# SAMC21N_Xplained_Pro_Level_Converters.net
KiCad netlist of a schematic drawn in Altium Designer
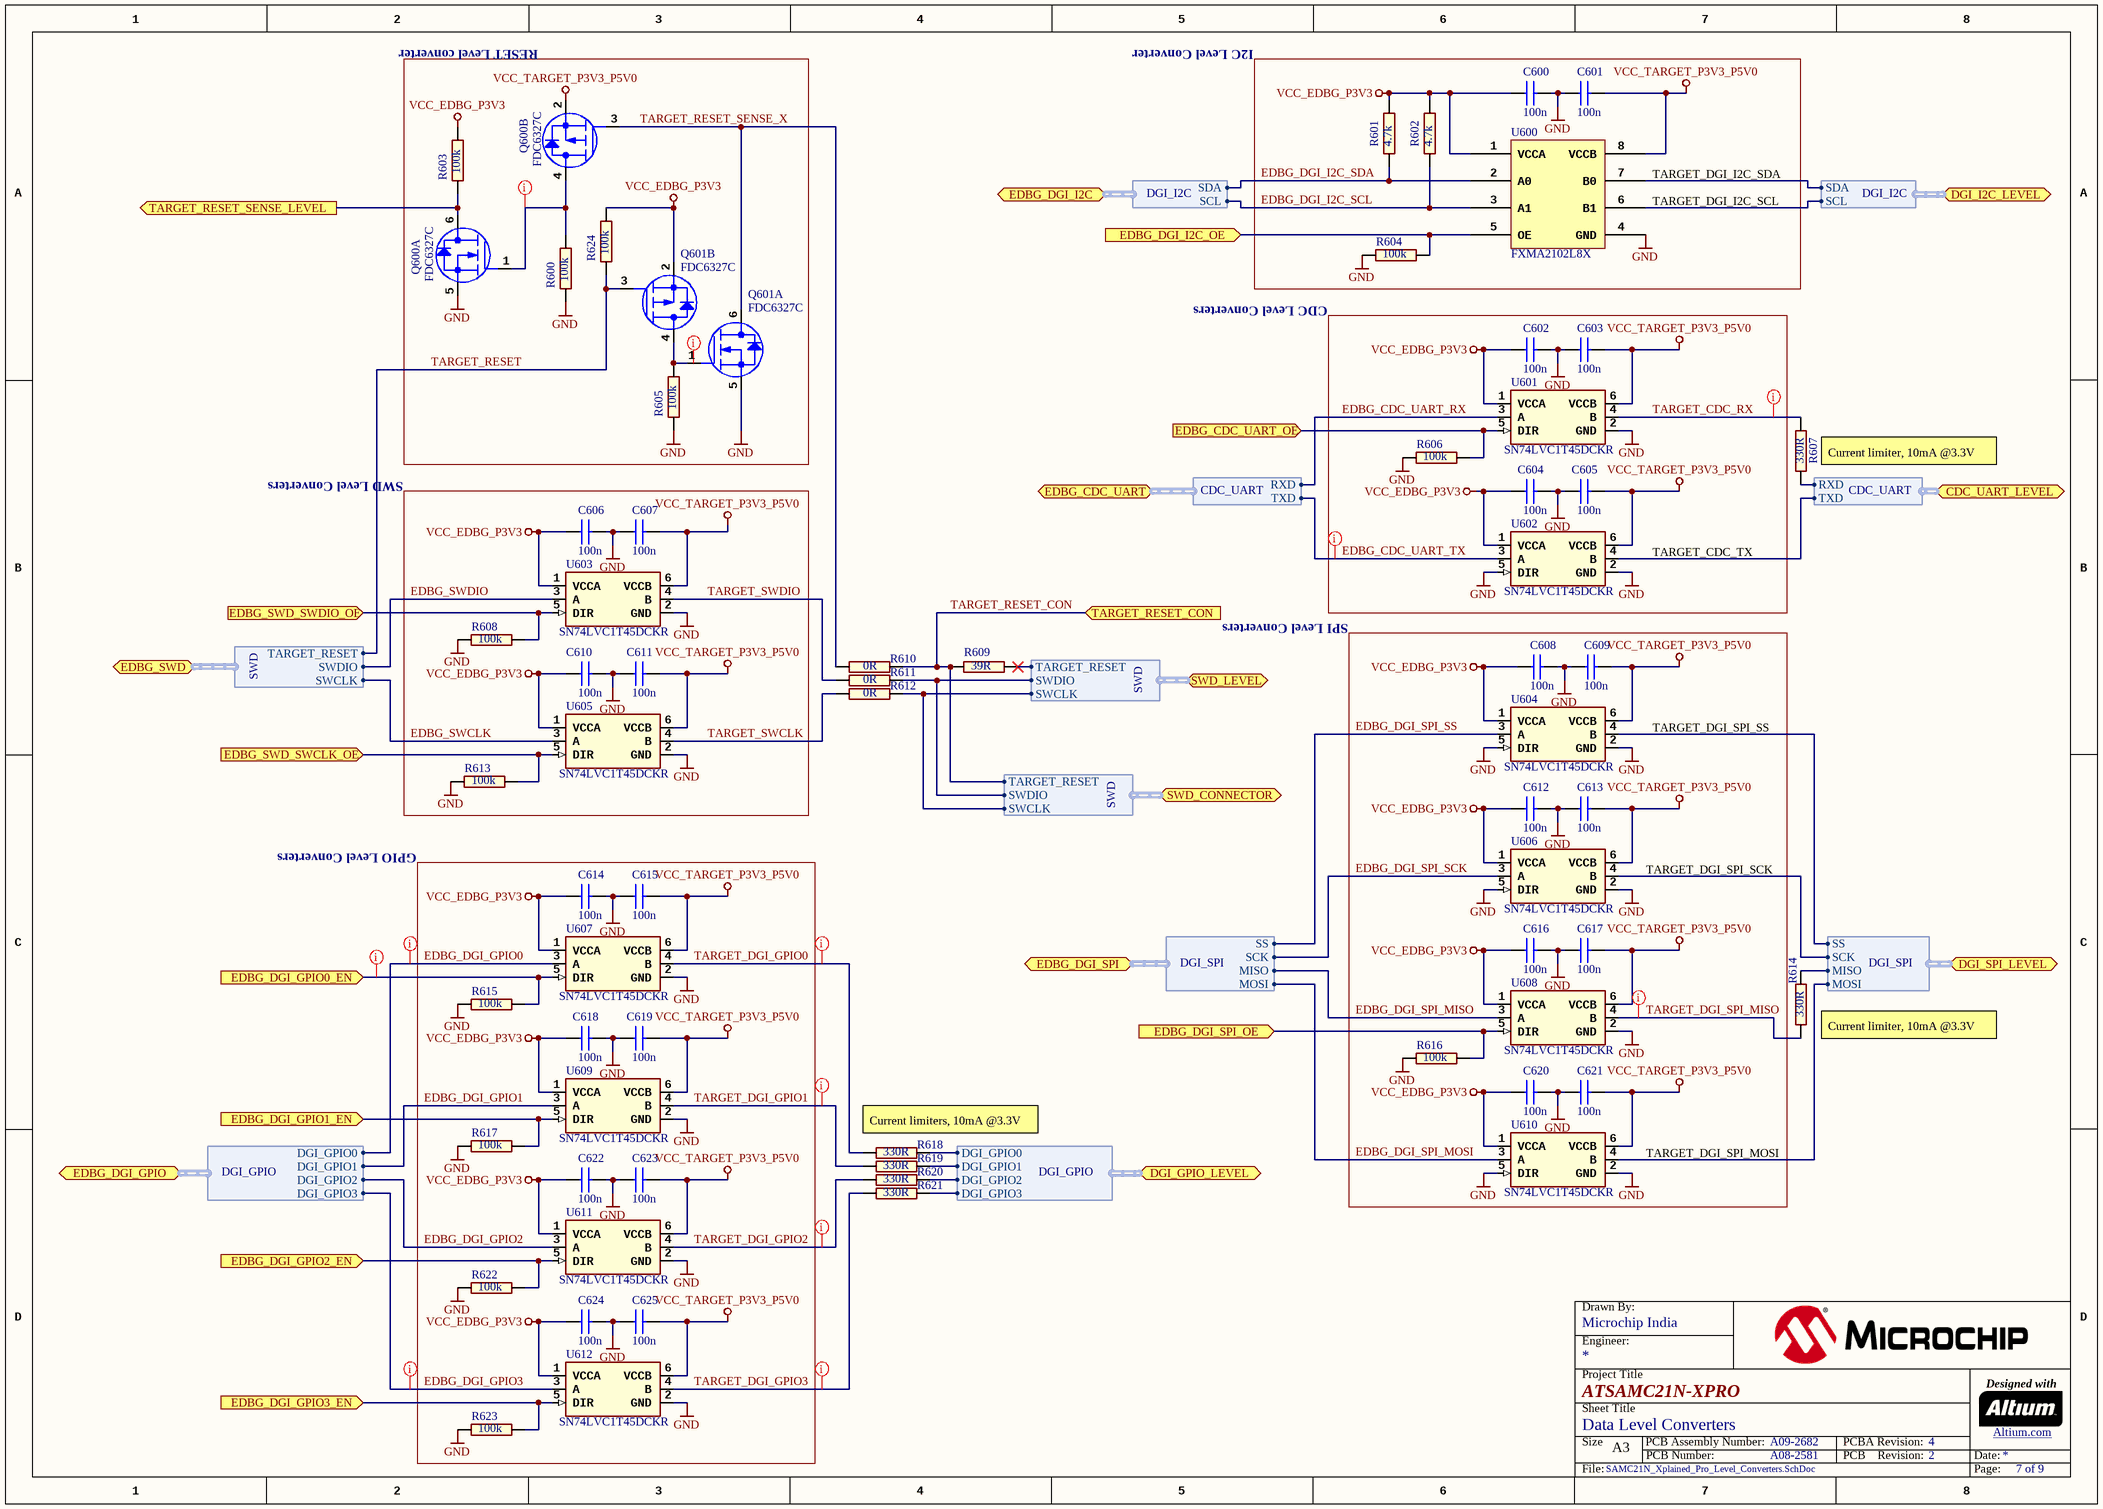
[diagram p0: SAMC21N_Xplained_Pro_Level_Converters.SchDoc]

(export (version "E")
  (design (tool "Eeschema 10.0.6"))
  (components
    (comp (ref "C600")
      (value "100n")
      (footprint "AP1-00053")
      (description "Ceramic capacitor, SMD 0402, X7R, 16V, +/-10%")
      (fields
        (field (name "TOLERANCE") "16V, +/-10%")
        (field (name "MANUFACTURER") "Kemet")
        (field (name "VERIFIED BY") "Lars Helge Mo")
      )
      (libsource (lib "AltiumDbLib") (part "CAP-NONPOL"))
    )
    (comp (ref "C601")
      (value "100n")
      (footprint "AP1-00053")
      (description "Ceramic capacitor, SMD 0402, X7R, 16V, +/-10%")
      (fields
        (field (name "TOLERANCE") "16V, +/-10%")
        (field (name "MANUFACTURER") "Kemet")
        (field (name "VERIFIED BY") "Lars Helge Mo")
      )
      (libsource (lib "AltiumDbLib") (part "CAP-NONPOL"))
    )
    (comp (ref "C602")
      (value "100n")
      (footprint "AP1-00053")
      (description "Ceramic capacitor, SMD 0402, X7R, 16V, +/-10%")
      (fields
        (field (name "TOLERANCE") "16V, +/-10%")
        (field (name "MANUFACTURER") "Kemet")
        (field (name "VERIFIED BY") "Lars Helge Mo")
      )
      (libsource (lib "AltiumDbLib") (part "CAP-NONPOL"))
    )
    (comp (ref "C603")
      (value "100n")
      (footprint "AP1-00053")
      (description "Ceramic capacitor, SMD 0402, X7R, 16V, +/-10%")
      (fields
        (field (name "TOLERANCE") "16V, +/-10%")
        (field (name "MANUFACTURER") "Kemet")
        (field (name "VERIFIED BY") "Lars Helge Mo")
      )
      (libsource (lib "AltiumDbLib") (part "CAP-NONPOL"))
    )
    (comp (ref "C604")
      (value "100n")
      (footprint "AP1-00053")
      (description "Ceramic capacitor, SMD 0402, X7R, 16V, +/-10%")
      (fields
        (field (name "TOLERANCE") "16V, +/-10%")
        (field (name "MANUFACTURER") "Kemet")
        (field (name "VERIFIED BY") "Lars Helge Mo")
      )
      (libsource (lib "AltiumDbLib") (part "CAP-NONPOL"))
    )
    (comp (ref "C605")
      (value "100n")
      (footprint "AP1-00053")
      (description "Ceramic capacitor, SMD 0402, X7R, 16V, +/-10%")
      (fields
        (field (name "TOLERANCE") "16V, +/-10%")
        (field (name "MANUFACTURER") "Kemet")
        (field (name "VERIFIED BY") "Lars Helge Mo")
      )
      (libsource (lib "AltiumDbLib") (part "CAP-NONPOL"))
    )
    (comp (ref "C606")
      (value "100n")
      (footprint "AP1-00053")
      (description "Ceramic capacitor, SMD 0402, X7R, 16V, +/-10%")
      (fields
        (field (name "TOLERANCE") "16V, +/-10%")
        (field (name "MANUFACTURER") "Kemet")
        (field (name "VERIFIED BY") "Lars Helge Mo")
      )
      (libsource (lib "AltiumDbLib") (part "CAP-NONPOL"))
    )
    (comp (ref "C607")
      (value "100n")
      (footprint "AP1-00053")
      (description "Ceramic capacitor, SMD 0402, X7R, 16V, +/-10%")
      (fields
        (field (name "TOLERANCE") "16V, +/-10%")
        (field (name "MANUFACTURER") "Kemet")
        (field (name "VERIFIED BY") "Lars Helge Mo")
      )
      (libsource (lib "AltiumDbLib") (part "CAP-NONPOL"))
    )
    (comp (ref "C608")
      (value "100n")
      (footprint "AP1-00053")
      (description "Ceramic capacitor, SMD 0402, X7R, 16V, +/-10%")
      (fields
        (field (name "TOLERANCE") "16V, +/-10%")
        (field (name "MANUFACTURER") "Kemet")
        (field (name "VERIFIED BY") "Lars Helge Mo")
      )
      (libsource (lib "AltiumDbLib") (part "CAP-NONPOL"))
    )
    (comp (ref "C609")
      (value "100n")
      (footprint "AP1-00053")
      (description "Ceramic capacitor, SMD 0402, X7R, 16V, +/-10%")
      (fields
        (field (name "TOLERANCE") "16V, +/-10%")
        (field (name "MANUFACTURER") "Kemet")
        (field (name "VERIFIED BY") "Lars Helge Mo")
      )
      (libsource (lib "AltiumDbLib") (part "CAP-NONPOL"))
    )
    (comp (ref "C610")
      (value "100n")
      (footprint "AP1-00053")
      (description "Ceramic capacitor, SMD 0402, X7R, 16V, +/-10%")
      (fields
        (field (name "TOLERANCE") "16V, +/-10%")
        (field (name "MANUFACTURER") "Kemet")
        (field (name "VERIFIED BY") "Lars Helge Mo")
      )
      (libsource (lib "AltiumDbLib") (part "CAP-NONPOL"))
    )
    (comp (ref "C611")
      (value "100n")
      (footprint "AP1-00053")
      (description "Ceramic capacitor, SMD 0402, X7R, 16V, +/-10%")
      (fields
        (field (name "TOLERANCE") "16V, +/-10%")
        (field (name "MANUFACTURER") "Kemet")
        (field (name "VERIFIED BY") "Lars Helge Mo")
      )
      (libsource (lib "AltiumDbLib") (part "CAP-NONPOL"))
    )
    (comp (ref "C612")
      (value "100n")
      (footprint "AP1-00053")
      (description "Ceramic capacitor, SMD 0402, X7R, 16V, +/-10%")
      (fields
        (field (name "TOLERANCE") "16V, +/-10%")
        (field (name "MANUFACTURER") "Kemet")
        (field (name "VERIFIED BY") "Lars Helge Mo")
      )
      (libsource (lib "AltiumDbLib") (part "CAP-NONPOL"))
    )
    (comp (ref "C613")
      (value "100n")
      (footprint "AP1-00053")
      (description "Ceramic capacitor, SMD 0402, X7R, 16V, +/-10%")
      (fields
        (field (name "TOLERANCE") "16V, +/-10%")
        (field (name "MANUFACTURER") "Kemet")
        (field (name "VERIFIED BY") "Lars Helge Mo")
      )
      (libsource (lib "AltiumDbLib") (part "CAP-NONPOL"))
    )
    (comp (ref "C614")
      (value "100n")
      (footprint "AP1-00053")
      (description "Ceramic capacitor, SMD 0402, X7R, 16V, +/-10%")
      (fields
        (field (name "TOLERANCE") "16V, +/-10%")
        (field (name "MANUFACTURER") "Kemet")
        (field (name "VERIFIED BY") "Lars Helge Mo")
      )
      (libsource (lib "AltiumDbLib") (part "CAP-NONPOL"))
    )
    (comp (ref "C615")
      (value "100n")
      (footprint "AP1-00053")
      (description "Ceramic capacitor, SMD 0402, X7R, 16V, +/-10%")
      (fields
        (field (name "TOLERANCE") "16V, +/-10%")
        (field (name "MANUFACTURER") "Kemet")
        (field (name "VERIFIED BY") "Lars Helge Mo")
      )
      (libsource (lib "AltiumDbLib") (part "CAP-NONPOL"))
    )
    (comp (ref "C616")
      (value "100n")
      (footprint "AP1-00053")
      (description "Ceramic capacitor, SMD 0402, X7R, 16V, +/-10%")
      (fields
        (field (name "TOLERANCE") "16V, +/-10%")
        (field (name "MANUFACTURER") "Kemet")
        (field (name "VERIFIED BY") "Lars Helge Mo")
      )
      (libsource (lib "AltiumDbLib") (part "CAP-NONPOL"))
    )
    (comp (ref "C617")
      (value "100n")
      (footprint "AP1-00053")
      (description "Ceramic capacitor, SMD 0402, X7R, 16V, +/-10%")
      (fields
        (field (name "TOLERANCE") "16V, +/-10%")
        (field (name "MANUFACTURER") "Kemet")
        (field (name "VERIFIED BY") "Lars Helge Mo")
      )
      (libsource (lib "AltiumDbLib") (part "CAP-NONPOL"))
    )
    (comp (ref "C618")
      (value "100n")
      (footprint "AP1-00053")
      (description "Ceramic capacitor, SMD 0402, X7R, 16V, +/-10%")
      (fields
        (field (name "TOLERANCE") "16V, +/-10%")
        (field (name "MANUFACTURER") "Kemet")
        (field (name "VERIFIED BY") "Lars Helge Mo")
      )
      (libsource (lib "AltiumDbLib") (part "CAP-NONPOL"))
    )
    (comp (ref "C619")
      (value "100n")
      (footprint "AP1-00053")
      (description "Ceramic capacitor, SMD 0402, X7R, 16V, +/-10%")
      (fields
        (field (name "TOLERANCE") "16V, +/-10%")
        (field (name "MANUFACTURER") "Kemet")
        (field (name "VERIFIED BY") "Lars Helge Mo")
      )
      (libsource (lib "AltiumDbLib") (part "CAP-NONPOL"))
    )
    (comp (ref "C620")
      (value "100n")
      (footprint "AP1-00053")
      (description "Ceramic capacitor, SMD 0402, X7R, 16V, +/-10%")
      (fields
        (field (name "TOLERANCE") "16V, +/-10%")
        (field (name "MANUFACTURER") "Kemet")
        (field (name "VERIFIED BY") "Lars Helge Mo")
      )
      (libsource (lib "AltiumDbLib") (part "CAP-NONPOL"))
    )
    (comp (ref "C621")
      (value "100n")
      (footprint "AP1-00053")
      (description "Ceramic capacitor, SMD 0402, X7R, 16V, +/-10%")
      (fields
        (field (name "TOLERANCE") "16V, +/-10%")
        (field (name "MANUFACTURER") "Kemet")
        (field (name "VERIFIED BY") "Lars Helge Mo")
      )
      (libsource (lib "AltiumDbLib") (part "CAP-NONPOL"))
    )
    (comp (ref "C622")
      (value "100n")
      (footprint "AP1-00053")
      (description "Ceramic capacitor, SMD 0402, X7R, 16V, +/-10%")
      (fields
        (field (name "TOLERANCE") "16V, +/-10%")
        (field (name "MANUFACTURER") "Kemet")
        (field (name "VERIFIED BY") "Lars Helge Mo")
      )
      (libsource (lib "AltiumDbLib") (part "CAP-NONPOL"))
    )
    (comp (ref "C623")
      (value "100n")
      (footprint "AP1-00053")
      (description "Ceramic capacitor, SMD 0402, X7R, 16V, +/-10%")
      (fields
        (field (name "TOLERANCE") "16V, +/-10%")
        (field (name "MANUFACTURER") "Kemet")
        (field (name "VERIFIED BY") "Lars Helge Mo")
      )
      (libsource (lib "AltiumDbLib") (part "CAP-NONPOL"))
    )
    (comp (ref "C624")
      (value "100n")
      (footprint "AP1-00053")
      (description "Ceramic capacitor, SMD 0402, X7R, 16V, +/-10%")
      (fields
        (field (name "TOLERANCE") "16V, +/-10%")
        (field (name "MANUFACTURER") "Kemet")
        (field (name "VERIFIED BY") "Lars Helge Mo")
      )
      (libsource (lib "AltiumDbLib") (part "CAP-NONPOL"))
    )
    (comp (ref "C625")
      (value "100n")
      (footprint "AP1-00053")
      (description "Ceramic capacitor, SMD 0402, X7R, 16V, +/-10%")
      (fields
        (field (name "TOLERANCE") "16V, +/-10%")
        (field (name "MANUFACTURER") "Kemet")
        (field (name "VERIFIED BY") "Lars Helge Mo")
      )
      (libsource (lib "AltiumDbLib") (part "CAP-NONPOL"))
    )
    (comp (ref "Q600")
      (value "FDC6327C")
      (footprint "AP5-00008")
      (fields (field (name "MANUFACTURER") "Fairchild") (field (name "Comment") "Farnell no: 9844856"))
      (libsource (lib "AltiumDbLib") (part "DUAL_NP_G1S2G2D2S1D1"))
    )
    (comp (ref "Q601")
      (value "FDC6327C")
      (footprint "AP5-00008")
      (fields (field (name "MANUFACTURER") "Fairchild") (field (name "Comment") "Farnell no: 9844856"))
      (libsource (lib "AltiumDbLib") (part "DUAL_NP_G1S2G2D2S1D1"))
    )
    (comp (ref "R600")
      (value "100k")
      (footprint "AP2-00011")
      (description "Thick film resistor, SMD 0402, 1/16W, 1%")
      (fields
        (field (name "TOLERANCE") "1 %")
        (field (name "Comment") "R2")
        (field (name "VERIFIED BY") "Lars Helge Mo")
      )
      (libsource (lib "") (part "R2_2"))
    )
    (comp (ref "R601")
      (value "4.7k")
      (footprint "AP2-00011")
      (description "Thick film resistor, SMD 0402, 1/16W, 1%")
      (fields
        (field (name "TOLERANCE") "1 %")
        (field (name "Comment") "R2")
        (field (name "VERIFIED BY") "Lars Helge Mo")
      )
      (libsource (lib "") (part "R2_2"))
    )
    (comp (ref "R602")
      (value "4.7k")
      (footprint "AP2-00011")
      (description "Thick film resistor, SMD 0402, 1/16W, 1%")
      (fields
        (field (name "TOLERANCE") "1 %")
        (field (name "Comment") "R2")
        (field (name "VERIFIED BY") "Lars Helge Mo")
      )
      (libsource (lib "") (part "R2_2"))
    )
    (comp (ref "R603")
      (value "100k")
      (footprint "AP2-00011")
      (description "Thick film resistor, SMD 0402, 1/16W, 1%")
      (fields
        (field (name "TOLERANCE") "1 %")
        (field (name "Comment") "R2")
        (field (name "VERIFIED BY") "Lars Helge Mo")
      )
      (libsource (lib "") (part "R2_2"))
    )
    (comp (ref "R604")
      (value "100k")
      (footprint "AP2-00011")
      (description "Thick film resistor, SMD 0402, 1/16W, 1%")
      (fields
        (field (name "TOLERANCE") "1 %")
        (field (name "Comment") "R2")
        (field (name "VERIFIED BY") "Lars Helge Mo")
      )
      (libsource (lib "AltiumDbLib") (part "R2"))
    )
    (comp (ref "R605")
      (value "100k")
      (footprint "AP2-00011")
      (description "Thick film resistor, SMD 0402, 1/16W, 1%")
      (fields
        (field (name "TOLERANCE") "1 %")
        (field (name "Comment") "R2")
        (field (name "VERIFIED BY") "Lars Helge Mo")
      )
      (libsource (lib "") (part "R2_2"))
    )
    (comp (ref "R606")
      (value "100k")
      (footprint "AP2-00011")
      (description "Thick film resistor, SMD 0402, 1/16W, 1%")
      (fields
        (field (name "TOLERANCE") "1 %")
        (field (name "Comment") "R2")
        (field (name "VERIFIED BY") "Lars Helge Mo")
      )
      (libsource (lib "") (part "R2_1"))
    )
    (comp (ref "R607")
      (value "330R")
      (footprint "AP2-00011")
      (description "Thick film resistor, SMD 0402, 1/16W, 1%")
      (fields
        (field (name "TOLERANCE") "1 %")
        (field (name "Comment") "R2")
        (field (name "VERIFIED BY") "Lars Helge Mo")
      )
      (libsource (lib "") (part "R2_2"))
    )
    (comp (ref "R608")
      (value "100k")
      (footprint "AP2-00011")
      (description "Thick film resistor, SMD 0402, 1/16W, 1%")
      (fields
        (field (name "TOLERANCE") "1 %")
        (field (name "Comment") "R2")
        (field (name "VERIFIED BY") "Lars Helge Mo")
      )
      (libsource (lib "") (part "R2_1"))
    )
    (comp (ref "R609")
      (value "39R")
      (footprint "AP2-00011")
      (description "Thick film resistor, SMD 0402, 1/16W, 1%")
      (fields
        (field (name "TOLERANCE") "1 %")
        (field (name "Comment") "R2")
        (field (name "VERIFIED BY") "Lars Helge Mo")
      )
      (libsource (lib "") (part "R2_3"))
    )
    (comp (ref "R610")
      (value "0R")
      (footprint "AP2-00000")
      (description "Thick film resistor, SMD 0402, 1/16W, 1%")
      (fields
        (field (name "TOLERANCE") "1 %")
        (field (name "Comment") "R2")
        (field (name "VERIFIED BY") "Lars Helge Mo")
      )
      (libsource (lib "AltiumDbLib") (part "R2"))
    )
    (comp (ref "R611")
      (value "0R")
      (footprint "AP2-00000")
      (description "Thick film resistor, SMD 0402, 1/16W, 1%")
      (fields
        (field (name "TOLERANCE") "1 %")
        (field (name "Comment") "R2")
        (field (name "VERIFIED BY") "Lars Helge Mo")
      )
      (libsource (lib "AltiumDbLib") (part "R2"))
    )
    (comp (ref "R612")
      (value "0R")
      (footprint "AP2-00000")
      (description "Thick film resistor, SMD 0402, 1/16W, 1%")
      (fields
        (field (name "TOLERANCE") "1 %")
        (field (name "Comment") "R2")
        (field (name "VERIFIED BY") "Lars Helge Mo")
      )
      (libsource (lib "AltiumDbLib") (part "R2"))
    )
    (comp (ref "R613")
      (value "100k")
      (footprint "AP2-00011")
      (description "Thick film resistor, SMD 0402, 1/16W, 1%")
      (fields
        (field (name "TOLERANCE") "1 %")
        (field (name "Comment") "R2")
        (field (name "VERIFIED BY") "Lars Helge Mo")
      )
      (libsource (lib "") (part "R2_1"))
    )
    (comp (ref "R614")
      (value "330R")
      (footprint "AP2-00011")
      (description "Thick film resistor, SMD 0402, 1/16W, 1%")
      (fields
        (field (name "TOLERANCE") "1 %")
        (field (name "Comment") "R2")
        (field (name "VERIFIED BY") "Lars Helge Mo")
      )
      (libsource (lib "") (part "R2_2"))
    )
    (comp (ref "R615")
      (value "100k")
      (footprint "AP2-00011")
      (description "Thick film resistor, SMD 0402, 1/16W, 1%")
      (fields
        (field (name "TOLERANCE") "1 %")
        (field (name "Comment") "R2")
        (field (name "VERIFIED BY") "Lars Helge Mo")
      )
      (libsource (lib "") (part "R2_1"))
    )
    (comp (ref "R616")
      (value "100k")
      (footprint "AP2-00011")
      (description "Thick film resistor, SMD 0402, 1/16W, 1%")
      (fields
        (field (name "TOLERANCE") "1 %")
        (field (name "Comment") "R2")
        (field (name "VERIFIED BY") "Lars Helge Mo")
      )
      (libsource (lib "") (part "R2_1"))
    )
    (comp (ref "R617")
      (value "100k")
      (footprint "AP2-00011")
      (description "Thick film resistor, SMD 0402, 1/16W, 1%")
      (fields
        (field (name "TOLERANCE") "1 %")
        (field (name "Comment") "R2")
        (field (name "VERIFIED BY") "Lars Helge Mo")
      )
      (libsource (lib "") (part "R2_1"))
    )
    (comp (ref "R618")
      (value "330R")
      (footprint "AP2-00011")
      (description "Thick film resistor, SMD 0402, 1/16W, 1%")
      (fields
        (field (name "TOLERANCE") "1 %")
        (field (name "Comment") "R2")
        (field (name "VERIFIED BY") "Lars Helge Mo")
      )
      (libsource (lib "AltiumDbLib") (part "R2"))
    )
    (comp (ref "R619")
      (value "330R")
      (footprint "AP2-00011")
      (description "Thick film resistor, SMD 0402, 1/16W, 1%")
      (fields
        (field (name "TOLERANCE") "1 %")
        (field (name "Comment") "R2")
        (field (name "VERIFIED BY") "Lars Helge Mo")
      )
      (libsource (lib "AltiumDbLib") (part "R2"))
    )
    (comp (ref "R620")
      (value "330R")
      (footprint "AP2-00011")
      (description "Thick film resistor, SMD 0402, 1/16W, 1%")
      (fields
        (field (name "TOLERANCE") "1 %")
        (field (name "Comment") "R2")
        (field (name "VERIFIED BY") "Lars Helge Mo")
      )
      (libsource (lib "AltiumDbLib") (part "R2"))
    )
    (comp (ref "R621")
      (value "330R")
      (footprint "AP2-00011")
      (description "Thick film resistor, SMD 0402, 1/16W, 1%")
      (fields
        (field (name "TOLERANCE") "1 %")
        (field (name "Comment") "R2")
        (field (name "VERIFIED BY") "Lars Helge Mo")
      )
      (libsource (lib "AltiumDbLib") (part "R2"))
    )
    (comp (ref "R622")
      (value "100k")
      (footprint "AP2-00011")
      (description "Thick film resistor, SMD 0402, 1/16W, 1%")
      (fields
        (field (name "TOLERANCE") "1 %")
        (field (name "Comment") "R2")
        (field (name "VERIFIED BY") "Lars Helge Mo")
      )
      (libsource (lib "") (part "R2_1"))
    )
    (comp (ref "R623")
      (value "100k")
      (footprint "AP2-00011")
      (description "Thick film resistor, SMD 0402, 1/16W, 1%")
      (fields
        (field (name "TOLERANCE") "1 %")
        (field (name "Comment") "R2")
        (field (name "VERIFIED BY") "Lars Helge Mo")
      )
      (libsource (lib "") (part "R2_1"))
    )
    (comp (ref "R624")
      (value "100k")
      (footprint "AP2-00011")
      (description "Thick film resistor, SMD 0402, 1/16W, 1%")
      (fields
        (field (name "TOLERANCE") "1 %")
        (field (name "Comment") "R2")
        (field (name "VERIFIED BY") "Lars Helge Mo")
      )
      (libsource (lib "") (part "R2_2"))
    )
    (comp (ref "U600")
      (value "FXMA2102L8X")
      (footprint "AP6-00258")
      (description "Dual supply, 2-bit, voltage translator, buffer, repeater, isolator for I2C applications")
      (fields (field (name "MANUFACTURER") "Fairchild") (field (name "Comment") "FXMA2102"))
      (libsource (lib "AltiumDbLib") (part "FXMA2102"))
    )
    (comp (ref "U601")
      (value "SN74LVC1T45DCKR")
      (footprint "AP6-00015")
      (description "Single-Bit Dual-Supply Bus Transceiver with Configurable Voltage Translation and 3-State Outputs")
      (fields
        (field (name "MANUFACTURER") "Texas Instruments")
        (field (name "VERIFIED BY") "Sveinung Helgeland")
      )
      (libsource (lib "AltiumDbLib") (part "SN74LVC1T45DCKR"))
    )
    (comp (ref "U602")
      (value "SN74LVC1T45DCKR")
      (footprint "AP6-00015")
      (description "Single-Bit Dual-Supply Bus Transceiver with Configurable Voltage Translation and 3-State Outputs")
      (fields
        (field (name "MANUFACTURER") "Texas Instruments")
        (field (name "VERIFIED BY") "Sveinung Helgeland")
      )
      (libsource (lib "AltiumDbLib") (part "SN74LVC1T45DCKR"))
    )
    (comp (ref "U603")
      (value "SN74LVC1T45DCKR")
      (footprint "AP6-00015")
      (description "Single-Bit Dual-Supply Bus Transceiver with Configurable Voltage Translation and 3-State Outputs")
      (fields
        (field (name "MANUFACTURER") "Texas Instruments")
        (field (name "VERIFIED BY") "Sveinung Helgeland")
      )
      (libsource (lib "AltiumDbLib") (part "SN74LVC1T45DCKR"))
    )
    (comp (ref "U604")
      (value "SN74LVC1T45DCKR")
      (footprint "AP6-00015")
      (description "Single-Bit Dual-Supply Bus Transceiver with Configurable Voltage Translation and 3-State Outputs")
      (fields
        (field (name "MANUFACTURER") "Texas Instruments")
        (field (name "VERIFIED BY") "Sveinung Helgeland")
      )
      (libsource (lib "AltiumDbLib") (part "SN74LVC1T45DCKR"))
    )
    (comp (ref "U605")
      (value "SN74LVC1T45DCKR")
      (footprint "AP6-00015")
      (description "Single-Bit Dual-Supply Bus Transceiver with Configurable Voltage Translation and 3-State Outputs")
      (fields
        (field (name "MANUFACTURER") "Texas Instruments")
        (field (name "VERIFIED BY") "Sveinung Helgeland")
      )
      (libsource (lib "AltiumDbLib") (part "SN74LVC1T45DCKR"))
    )
    (comp (ref "U606")
      (value "SN74LVC1T45DCKR")
      (footprint "AP6-00015")
      (description "Single-Bit Dual-Supply Bus Transceiver with Configurable Voltage Translation and 3-State Outputs")
      (fields
        (field (name "MANUFACTURER") "Texas Instruments")
        (field (name "VERIFIED BY") "Sveinung Helgeland")
      )
      (libsource (lib "AltiumDbLib") (part "SN74LVC1T45DCKR"))
    )
    (comp (ref "U607")
      (value "SN74LVC1T45DCKR")
      (footprint "AP6-00015")
      (description "Single-Bit Dual-Supply Bus Transceiver with Configurable Voltage Translation and 3-State Outputs")
      (fields
        (field (name "MANUFACTURER") "Texas Instruments")
        (field (name "VERIFIED BY") "Sveinung Helgeland")
      )
      (libsource (lib "AltiumDbLib") (part "SN74LVC1T45DCKR"))
    )
    (comp (ref "U608")
      (value "SN74LVC1T45DCKR")
      (footprint "AP6-00015")
      (description "Single-Bit Dual-Supply Bus Transceiver with Configurable Voltage Translation and 3-State Outputs")
      (fields
        (field (name "MANUFACTURER") "Texas Instruments")
        (field (name "VERIFIED BY") "Sveinung Helgeland")
      )
      (libsource (lib "AltiumDbLib") (part "SN74LVC1T45DCKR"))
    )
    (comp (ref "U609")
      (value "SN74LVC1T45DCKR")
      (footprint "AP6-00015")
      (description "Single-Bit Dual-Supply Bus Transceiver with Configurable Voltage Translation and 3-State Outputs")
      (fields
        (field (name "MANUFACTURER") "Texas Instruments")
        (field (name "VERIFIED BY") "Sveinung Helgeland")
      )
      (libsource (lib "AltiumDbLib") (part "SN74LVC1T45DCKR"))
    )
    (comp (ref "U610")
      (value "SN74LVC1T45DCKR")
      (footprint "AP6-00015")
      (description "Single-Bit Dual-Supply Bus Transceiver with Configurable Voltage Translation and 3-State Outputs")
      (fields
        (field (name "MANUFACTURER") "Texas Instruments")
        (field (name "VERIFIED BY") "Sveinung Helgeland")
      )
      (libsource (lib "AltiumDbLib") (part "SN74LVC1T45DCKR"))
    )
    (comp (ref "U611")
      (value "SN74LVC1T45DCKR")
      (footprint "AP6-00015")
      (description "Single-Bit Dual-Supply Bus Transceiver with Configurable Voltage Translation and 3-State Outputs")
      (fields
        (field (name "MANUFACTURER") "Texas Instruments")
        (field (name "VERIFIED BY") "Sveinung Helgeland")
      )
      (libsource (lib "AltiumDbLib") (part "SN74LVC1T45DCKR"))
    )
    (comp (ref "U612")
      (value "SN74LVC1T45DCKR")
      (footprint "AP6-00015")
      (description "Single-Bit Dual-Supply Bus Transceiver with Configurable Voltage Translation and 3-State Outputs")
      (fields
        (field (name "MANUFACTURER") "Texas Instruments")
        (field (name "VERIFIED BY") "Sveinung Helgeland")
      )
      (libsource (lib "AltiumDbLib") (part "SN74LVC1T45DCKR"))
    )
  )
  (nets
    (net (code "6") (name "/EDBG_CDC_UART_OE") (class "Default")
      (node (ref "R606") (pin "1") (pinfunction "1_1") (pintype "passive"))
      (node (ref "U601") (pin "5") (pinfunction "DIR_5") (pintype "input"))
    )
    (net (code "7") (name "/EDBG_CDC_UART_RX") (class "Default")
      (node (ref "U601") (pin "3") (pinfunction "A_3") (pintype "bidirectional"))
    )
    (net (code "8") (name "/EDBG_CDC_UART_TX") (class "Default")
      (node (ref "U602") (pin "3") (pinfunction "A_3") (pintype "bidirectional"))
    )
    (net (code "9") (name "/EDBG_DGI_GPIO0") (class "Default")
      (node (ref "U607") (pin "3") (pinfunction "A_3") (pintype "bidirectional"))
    )
    (net (code "10") (name "/EDBG_DGI_GPIO0_EN") (class "Default")
      (node (ref "R615") (pin "1") (pinfunction "1_1") (pintype "passive"))
      (node (ref "U607") (pin "5") (pinfunction "DIR_5") (pintype "input"))
    )
    (net (code "11") (name "/EDBG_DGI_GPIO1") (class "Default")
      (node (ref "U609") (pin "3") (pinfunction "A_3") (pintype "bidirectional"))
    )
    (net (code "12") (name "/EDBG_DGI_GPIO1_EN") (class "Default")
      (node (ref "R617") (pin "1") (pinfunction "1_1") (pintype "passive"))
      (node (ref "U609") (pin "5") (pinfunction "DIR_5") (pintype "input"))
    )
    (net (code "13") (name "/EDBG_DGI_GPIO2") (class "Default")
      (node (ref "U611") (pin "3") (pinfunction "A_3") (pintype "bidirectional"))
    )
    (net (code "14") (name "/EDBG_DGI_GPIO2_EN") (class "Default")
      (node (ref "R622") (pin "1") (pinfunction "1_1") (pintype "passive"))
      (node (ref "U611") (pin "5") (pinfunction "DIR_5") (pintype "input"))
    )
    (net (code "15") (name "/EDBG_DGI_GPIO3") (class "Default")
      (node (ref "U612") (pin "3") (pinfunction "A_3") (pintype "bidirectional"))
    )
    (net (code "16") (name "/EDBG_DGI_GPIO3_EN") (class "Default")
      (node (ref "R623") (pin "1") (pinfunction "1_1") (pintype "passive"))
      (node (ref "U612") (pin "5") (pinfunction "DIR_5") (pintype "input"))
    )
    (net (code "17") (name "/EDBG_DGI_I2C_OE") (class "Default")
      (node (ref "R604") (pin "2") (pinfunction "2_2") (pintype "passive"))
      (node (ref "U600") (pin "5") (pinfunction "OE_5") (pintype "passive"))
    )
    (net (code "18") (name "/EDBG_DGI_I2C_SCL") (class "Default")
      (node (ref "R602") (pin "1") (pinfunction "1_1") (pintype "passive"))
      (node (ref "U600") (pin "3") (pinfunction "A1_3") (pintype "open_collector"))
    )
    (net (code "19") (name "/EDBG_DGI_I2C_SDA") (class "Default")
      (node (ref "R601") (pin "1") (pinfunction "1_1") (pintype "passive"))
      (node (ref "U600") (pin "2") (pinfunction "A0_2") (pintype "open_collector"))
    )
    (net (code "20") (name "/EDBG_DGI_SPI_MISO") (class "Default")
      (node (ref "U608") (pin "3") (pinfunction "A_3") (pintype "bidirectional"))
    )
    (net (code "21") (name "/EDBG_DGI_SPI_MOSI") (class "Default")
      (node (ref "U610") (pin "3") (pinfunction "A_3") (pintype "bidirectional"))
    )
    (net (code "22") (name "/EDBG_DGI_SPI_OE") (class "Default")
      (node (ref "R616") (pin "1") (pinfunction "1_1") (pintype "passive"))
      (node (ref "U608") (pin "5") (pinfunction "DIR_5") (pintype "input"))
    )
    (net (code "23") (name "/EDBG_DGI_SPI_SCK") (class "Default")
      (node (ref "U606") (pin "3") (pinfunction "A_3") (pintype "bidirectional"))
    )
    (net (code "24") (name "/EDBG_DGI_SPI_SS") (class "Default")
      (node (ref "U604") (pin "3") (pinfunction "A_3") (pintype "bidirectional"))
    )
    (net (code "25") (name "/EDBG_SWCLK") (class "Default")
      (node (ref "U605") (pin "3") (pinfunction "A_3") (pintype "bidirectional"))
    )
    (net (code "26") (name "/EDBG_SWDIO") (class "Default")
      (node (ref "U603") (pin "3") (pinfunction "A_3") (pintype "bidirectional"))
    )
    (net (code "27") (name "/EDBG_SWD_SWCLK_OE") (class "Default")
      (node (ref "R613") (pin "1") (pinfunction "1_1") (pintype "passive"))
      (node (ref "U605") (pin "5") (pinfunction "DIR_5") (pintype "input"))
    )
    (net (code "28") (name "/EDBG_SWD_SWDIO_OE") (class "Default")
      (node (ref "R608") (pin "1") (pinfunction "1_1") (pintype "passive"))
      (node (ref "U603") (pin "5") (pinfunction "DIR_5") (pintype "input"))
    )
    (net (code "29") (name "/TARGET_CDC_RX") (class "Default")
      (node (ref "R607") (pin "2") (pinfunction "2_2") (pintype "passive"))
      (node (ref "U601") (pin "4") (pinfunction "B_4") (pintype "bidirectional"))
    )
    (net (code "30") (name "/TARGET_DGI_GPIO0") (class "Default")
      (node (ref "R618") (pin "1") (pinfunction "1_1") (pintype "passive"))
      (node (ref "U607") (pin "4") (pinfunction "B_4") (pintype "bidirectional"))
    )
    (net (code "31") (name "/TARGET_DGI_GPIO1") (class "Default")
      (node (ref "R619") (pin "1") (pinfunction "1_1") (pintype "passive"))
      (node (ref "U609") (pin "4") (pinfunction "B_4") (pintype "bidirectional"))
    )
    (net (code "32") (name "/TARGET_DGI_GPIO2") (class "Default")
      (node (ref "R620") (pin "1") (pinfunction "1_1") (pintype "passive"))
      (node (ref "U611") (pin "4") (pinfunction "B_4") (pintype "bidirectional"))
    )
    (net (code "33") (name "/TARGET_DGI_GPIO3") (class "Default")
      (node (ref "R621") (pin "1") (pinfunction "1_1") (pintype "passive"))
      (node (ref "U612") (pin "4") (pinfunction "B_4") (pintype "bidirectional"))
    )
    (net (code "34") (name "/TARGET_DGI_SPI_MISO") (class "Default")
      (node (ref "R614") (pin "1") (pinfunction "1_1") (pintype "passive"))
      (node (ref "U608") (pin "4") (pinfunction "B_4") (pintype "bidirectional"))
    )
    (net (code "35") (name "/TARGET_RESET") (class "Default")
      (node (ref "Q601") (pin "3") (pinfunction "G_3") (pintype "passive"))
      (node (ref "R624") (pin "1") (pinfunction "1_1") (pintype "passive"))
    )
    (net (code "36") (name "/TARGET_RESET_CON") (class "Default")
      (node (ref "R609") (pin "1") (pinfunction "1_1") (pintype "passive"))
      (node (ref "R610") (pin "2") (pinfunction "2_2") (pintype "passive"))
    )
    (net (code "37") (name "/TARGET_RESET_SENSE_LEVEL") (class "Default")
      (node (ref "Q600") (pin "6") (pinfunction "D_6") (pintype "passive"))
      (node (ref "R603") (pin "1") (pinfunction "1_1") (pintype "passive"))
    )
    (net (code "38") (name "/TARGET_RESET_SENSE_X") (class "Default")
      (node (ref "Q600") (pin "3") (pinfunction "G_3") (pintype "passive"))
      (node (ref "Q601") (pin "6") (pinfunction "D_6") (pintype "passive"))
      (node (ref "R610") (pin "1") (pinfunction "1_1") (pintype "passive"))
    )
    (net (code "39") (name "/TARGET_SWCLK") (class "Default")
      (node (ref "R612") (pin "1") (pinfunction "1_1") (pintype "passive"))
      (node (ref "U605") (pin "4") (pinfunction "B_4") (pintype "bidirectional"))
    )
    (net (code "40") (name "/TARGET_SWDIO") (class "Default")
      (node (ref "R611") (pin "1") (pinfunction "1_1") (pintype "passive"))
      (node (ref "U603") (pin "4") (pinfunction "B_4") (pintype "bidirectional"))
    )
    (net (code "46") (name "GND") (class "Default")
      (node (ref "C600") (pin "2") (pinfunction "2_2") (pintype "passive"))
      (node (ref "C601") (pin "1") (pinfunction "1_1") (pintype "passive"))
      (node (ref "C602") (pin "2") (pinfunction "2_2") (pintype "passive"))
      (node (ref "C603") (pin "1") (pinfunction "1_1") (pintype "passive"))
      (node (ref "C604") (pin "2") (pinfunction "2_2") (pintype "passive"))
      (node (ref "C605") (pin "1") (pinfunction "1_1") (pintype "passive"))
      (node (ref "C606") (pin "2") (pinfunction "2_2") (pintype "passive"))
      (node (ref "C607") (pin "1") (pinfunction "1_1") (pintype "passive"))
      (node (ref "C608") (pin "2") (pinfunction "2_2") (pintype "passive"))
      (node (ref "C609") (pin "1") (pinfunction "1_1") (pintype "passive"))
      (node (ref "C610") (pin "2") (pinfunction "2_2") (pintype "passive"))
      (node (ref "C611") (pin "1") (pinfunction "1_1") (pintype "passive"))
      (node (ref "C612") (pin "2") (pinfunction "2_2") (pintype "passive"))
      (node (ref "C613") (pin "1") (pinfunction "1_1") (pintype "passive"))
      (node (ref "C614") (pin "2") (pinfunction "2_2") (pintype "passive"))
      (node (ref "C615") (pin "1") (pinfunction "1_1") (pintype "passive"))
      (node (ref "C616") (pin "2") (pinfunction "2_2") (pintype "passive"))
      (node (ref "C617") (pin "1") (pinfunction "1_1") (pintype "passive"))
      (node (ref "C618") (pin "2") (pinfunction "2_2") (pintype "passive"))
      (node (ref "C619") (pin "1") (pinfunction "1_1") (pintype "passive"))
      (node (ref "C620") (pin "2") (pinfunction "2_2") (pintype "passive"))
      (node (ref "C621") (pin "1") (pinfunction "1_1") (pintype "passive"))
      (node (ref "C622") (pin "2") (pinfunction "2_2") (pintype "passive"))
      (node (ref "C623") (pin "1") (pinfunction "1_1") (pintype "passive"))
      (node (ref "C624") (pin "2") (pinfunction "2_2") (pintype "passive"))
      (node (ref "C625") (pin "1") (pinfunction "1_1") (pintype "passive"))
      (node (ref "Q600") (pin "5") (pinfunction "S_5") (pintype "passive"))
      (node (ref "Q601") (pin "5") (pinfunction "S_5") (pintype "passive"))
      (node (ref "R600") (pin "1") (pinfunction "1_1") (pintype "passive"))
      (node (ref "R604") (pin "1") (pinfunction "1_1") (pintype "passive"))
      (node (ref "R605") (pin "1") (pinfunction "1_1") (pintype "passive"))
      (node (ref "R606") (pin "2") (pinfunction "2_2") (pintype "passive"))
      (node (ref "R608") (pin "2") (pinfunction "2_2") (pintype "passive"))
      (node (ref "R613") (pin "2") (pinfunction "2_2") (pintype "passive"))
      (node (ref "R615") (pin "2") (pinfunction "2_2") (pintype "passive"))
      (node (ref "R616") (pin "2") (pinfunction "2_2") (pintype "passive"))
      (node (ref "R617") (pin "2") (pinfunction "2_2") (pintype "passive"))
      (node (ref "R622") (pin "2") (pinfunction "2_2") (pintype "passive"))
      (node (ref "R623") (pin "2") (pinfunction "2_2") (pintype "passive"))
      (node (ref "U600") (pin "4") (pinfunction "GND_4") (pintype "power_in"))
      (node (ref "U601") (pin "2") (pinfunction "GND_2") (pintype "power_in"))
      (node (ref "U602") (pin "2") (pinfunction "GND_2") (pintype "power_in"))
      (node (ref "U602") (pin "5") (pinfunction "DIR_5") (pintype "input"))
      (node (ref "U603") (pin "2") (pinfunction "GND_2") (pintype "power_in"))
      (node (ref "U604") (pin "2") (pinfunction "GND_2") (pintype "power_in"))
      (node (ref "U604") (pin "5") (pinfunction "DIR_5") (pintype "input"))
      (node (ref "U605") (pin "2") (pinfunction "GND_2") (pintype "power_in"))
      (node (ref "U606") (pin "2") (pinfunction "GND_2") (pintype "power_in"))
      (node (ref "U606") (pin "5") (pinfunction "DIR_5") (pintype "input"))
      (node (ref "U607") (pin "2") (pinfunction "GND_2") (pintype "power_in"))
      (node (ref "U608") (pin "2") (pinfunction "GND_2") (pintype "power_in"))
      (node (ref "U609") (pin "2") (pinfunction "GND_2") (pintype "power_in"))
      (node (ref "U610") (pin "2") (pinfunction "GND_2") (pintype "power_in"))
      (node (ref "U610") (pin "5") (pinfunction "DIR_5") (pintype "input"))
      (node (ref "U611") (pin "2") (pinfunction "GND_2") (pintype "power_in"))
      (node (ref "U612") (pin "2") (pinfunction "GND_2") (pintype "power_in"))
    )
    (net (code "47") (name "Net-(Q600A-G)") (class "Default")
      (node (ref "Q600") (pin "1") (pinfunction "G_1") (pintype "passive"))
      (node (ref "Q600") (pin "4") (pinfunction "D_4") (pintype "passive"))
      (node (ref "R600") (pin "2") (pinfunction "2_2") (pintype "passive"))
    )
    (net (code "48") (name "Net-(Q601A-G)") (class "Default")
      (node (ref "Q601") (pin "1") (pinfunction "G_1") (pintype "passive"))
      (node (ref "Q601") (pin "4") (pinfunction "D_4") (pintype "passive"))
      (node (ref "R605") (pin "2") (pinfunction "2_2") (pintype "passive"))
    )
    (net (code "49") (name "VCC_EDBG_P3V3") (class "Default")
      (node (ref "C600") (pin "1") (pinfunction "1_1") (pintype "passive"))
      (node (ref "C602") (pin "1") (pinfunction "1_1") (pintype "passive"))
      (node (ref "C604") (pin "1") (pinfunction "1_1") (pintype "passive"))
      (node (ref "C606") (pin "1") (pinfunction "1_1") (pintype "passive"))
      (node (ref "C608") (pin "1") (pinfunction "1_1") (pintype "passive"))
      (node (ref "C610") (pin "1") (pinfunction "1_1") (pintype "passive"))
      (node (ref "C612") (pin "1") (pinfunction "1_1") (pintype "passive"))
      (node (ref "C614") (pin "1") (pinfunction "1_1") (pintype "passive"))
      (node (ref "C616") (pin "1") (pinfunction "1_1") (pintype "passive"))
      (node (ref "C618") (pin "1") (pinfunction "1_1") (pintype "passive"))
      (node (ref "C620") (pin "1") (pinfunction "1_1") (pintype "passive"))
      (node (ref "C622") (pin "1") (pinfunction "1_1") (pintype "passive"))
      (node (ref "C624") (pin "1") (pinfunction "1_1") (pintype "passive"))
      (node (ref "Q601") (pin "2") (pinfunction "S_2") (pintype "passive"))
      (node (ref "R601") (pin "2") (pinfunction "2_2") (pintype "passive"))
      (node (ref "R602") (pin "2") (pinfunction "2_2") (pintype "passive"))
      (node (ref "R603") (pin "2") (pinfunction "2_2") (pintype "passive"))
      (node (ref "R624") (pin "2") (pinfunction "2_2") (pintype "passive"))
      (node (ref "U600") (pin "1") (pinfunction "VCCA_1") (pintype "power_in"))
      (node (ref "U601") (pin "1") (pinfunction "VCCA_1") (pintype "power_in"))
      (node (ref "U602") (pin "1") (pinfunction "VCCA_1") (pintype "power_in"))
      (node (ref "U603") (pin "1") (pinfunction "VCCA_1") (pintype "power_in"))
      (node (ref "U604") (pin "1") (pinfunction "VCCA_1") (pintype "power_in"))
      (node (ref "U605") (pin "1") (pinfunction "VCCA_1") (pintype "power_in"))
      (node (ref "U606") (pin "1") (pinfunction "VCCA_1") (pintype "power_in"))
      (node (ref "U607") (pin "1") (pinfunction "VCCA_1") (pintype "power_in"))
      (node (ref "U608") (pin "1") (pinfunction "VCCA_1") (pintype "power_in"))
      (node (ref "U609") (pin "1") (pinfunction "VCCA_1") (pintype "power_in"))
      (node (ref "U610") (pin "1") (pinfunction "VCCA_1") (pintype "power_in"))
      (node (ref "U611") (pin "1") (pinfunction "VCCA_1") (pintype "power_in"))
      (node (ref "U612") (pin "1") (pinfunction "VCCA_1") (pintype "power_in"))
    )
    (net (code "50") (name "VCC_TARGET_P3V3_P5V0") (class "Default")
      (node (ref "C601") (pin "2") (pinfunction "2_2") (pintype "passive"))
      (node (ref "C603") (pin "2") (pinfunction "2_2") (pintype "passive"))
      (node (ref "C605") (pin "2") (pinfunction "2_2") (pintype "passive"))
      (node (ref "C607") (pin "2") (pinfunction "2_2") (pintype "passive"))
      (node (ref "C609") (pin "2") (pinfunction "2_2") (pintype "passive"))
      (node (ref "C611") (pin "2") (pinfunction "2_2") (pintype "passive"))
      (node (ref "C613") (pin "2") (pinfunction "2_2") (pintype "passive"))
      (node (ref "C615") (pin "2") (pinfunction "2_2") (pintype "passive"))
      (node (ref "C617") (pin "2") (pinfunction "2_2") (pintype "passive"))
      (node (ref "C619") (pin "2") (pinfunction "2_2") (pintype "passive"))
      (node (ref "C621") (pin "2") (pinfunction "2_2") (pintype "passive"))
      (node (ref "C623") (pin "2") (pinfunction "2_2") (pintype "passive"))
      (node (ref "C625") (pin "2") (pinfunction "2_2") (pintype "passive"))
      (node (ref "Q600") (pin "2") (pinfunction "S_2") (pintype "passive"))
      (node (ref "U600") (pin "8") (pinfunction "VCCB_8") (pintype "power_in"))
      (node (ref "U601") (pin "6") (pinfunction "VCCB_6") (pintype "power_in"))
      (node (ref "U602") (pin "6") (pinfunction "VCCB_6") (pintype "power_in"))
      (node (ref "U603") (pin "6") (pinfunction "VCCB_6") (pintype "power_in"))
      (node (ref "U604") (pin "6") (pinfunction "VCCB_6") (pintype "power_in"))
      (node (ref "U605") (pin "6") (pinfunction "VCCB_6") (pintype "power_in"))
      (node (ref "U606") (pin "6") (pinfunction "VCCB_6") (pintype "power_in"))
      (node (ref "U607") (pin "6") (pinfunction "VCCB_6") (pintype "power_in"))
      (node (ref "U608") (pin "6") (pinfunction "VCCB_6") (pintype "power_in"))
      (node (ref "U609") (pin "6") (pinfunction "VCCB_6") (pintype "power_in"))
      (node (ref "U610") (pin "6") (pinfunction "VCCB_6") (pintype "power_in"))
      (node (ref "U611") (pin "6") (pinfunction "VCCB_6") (pintype "power_in"))
      (node (ref "U612") (pin "6") (pinfunction "VCCB_6") (pintype "power_in"))
    )
    (net (code "51") (name "unconnected-(R607-Pad1)") (class "Default")
      (node (ref "R607") (pin "1") (pinfunction "1_1") (pintype "passive"))
    )
    (net (code "52") (name "unconnected-(R609-Pad2)") (class "Default")
      (node (ref "R609") (pin "2") (pinfunction "2_2") (pintype "passive+no_connect"))
    )
    (net (code "53") (name "unconnected-(R611-Pad2)") (class "Default")
      (node (ref "R611") (pin "2") (pinfunction "2_2") (pintype "passive"))
    )
    (net (code "54") (name "unconnected-(R612-Pad2)") (class "Default")
      (node (ref "R612") (pin "2") (pinfunction "2_2") (pintype "passive"))
    )
    (net (code "55") (name "unconnected-(R614-Pad2)") (class "Default")
      (node (ref "R614") (pin "2") (pinfunction "2_2") (pintype "passive"))
    )
    (net (code "56") (name "unconnected-(R618-Pad2)") (class "Default")
      (node (ref "R618") (pin "2") (pinfunction "2_2") (pintype "passive"))
    )
    (net (code "57") (name "unconnected-(R619-Pad2)") (class "Default")
      (node (ref "R619") (pin "2") (pinfunction "2_2") (pintype "passive"))
    )
    (net (code "58") (name "unconnected-(R620-Pad2)") (class "Default")
      (node (ref "R620") (pin "2") (pinfunction "2_2") (pintype "passive"))
    )
    (net (code "59") (name "unconnected-(R621-Pad2)") (class "Default")
      (node (ref "R621") (pin "2") (pinfunction "2_2") (pintype "passive"))
    )
    (net (code "60") (name "unconnected-(U600-B0-Pad7)") (class "Default")
      (node (ref "U600") (pin "7") (pinfunction "B0_7") (pintype "open_collector"))
    )
    (net (code "61") (name "unconnected-(U600-B1-Pad6)") (class "Default")
      (node (ref "U600") (pin "6") (pinfunction "B1_6") (pintype "open_collector"))
    )
    (net (code "62") (name "unconnected-(U602-B-Pad4)") (class "Default")
      (node (ref "U602") (pin "4") (pinfunction "B_4") (pintype "bidirectional"))
    )
    (net (code "63") (name "unconnected-(U604-B-Pad4)") (class "Default")
      (node (ref "U604") (pin "4") (pinfunction "B_4") (pintype "bidirectional"))
    )
    (net (code "64") (name "unconnected-(U606-B-Pad4)") (class "Default")
      (node (ref "U606") (pin "4") (pinfunction "B_4") (pintype "bidirectional"))
    )
    (net (code "65") (name "unconnected-(U610-B-Pad4)") (class "Default")
      (node (ref "U610") (pin "4") (pinfunction "B_4") (pintype "bidirectional"))
    )
  )
)
